# peripherals.net
KiCad netlist of a schematic drawn in Altium Designer
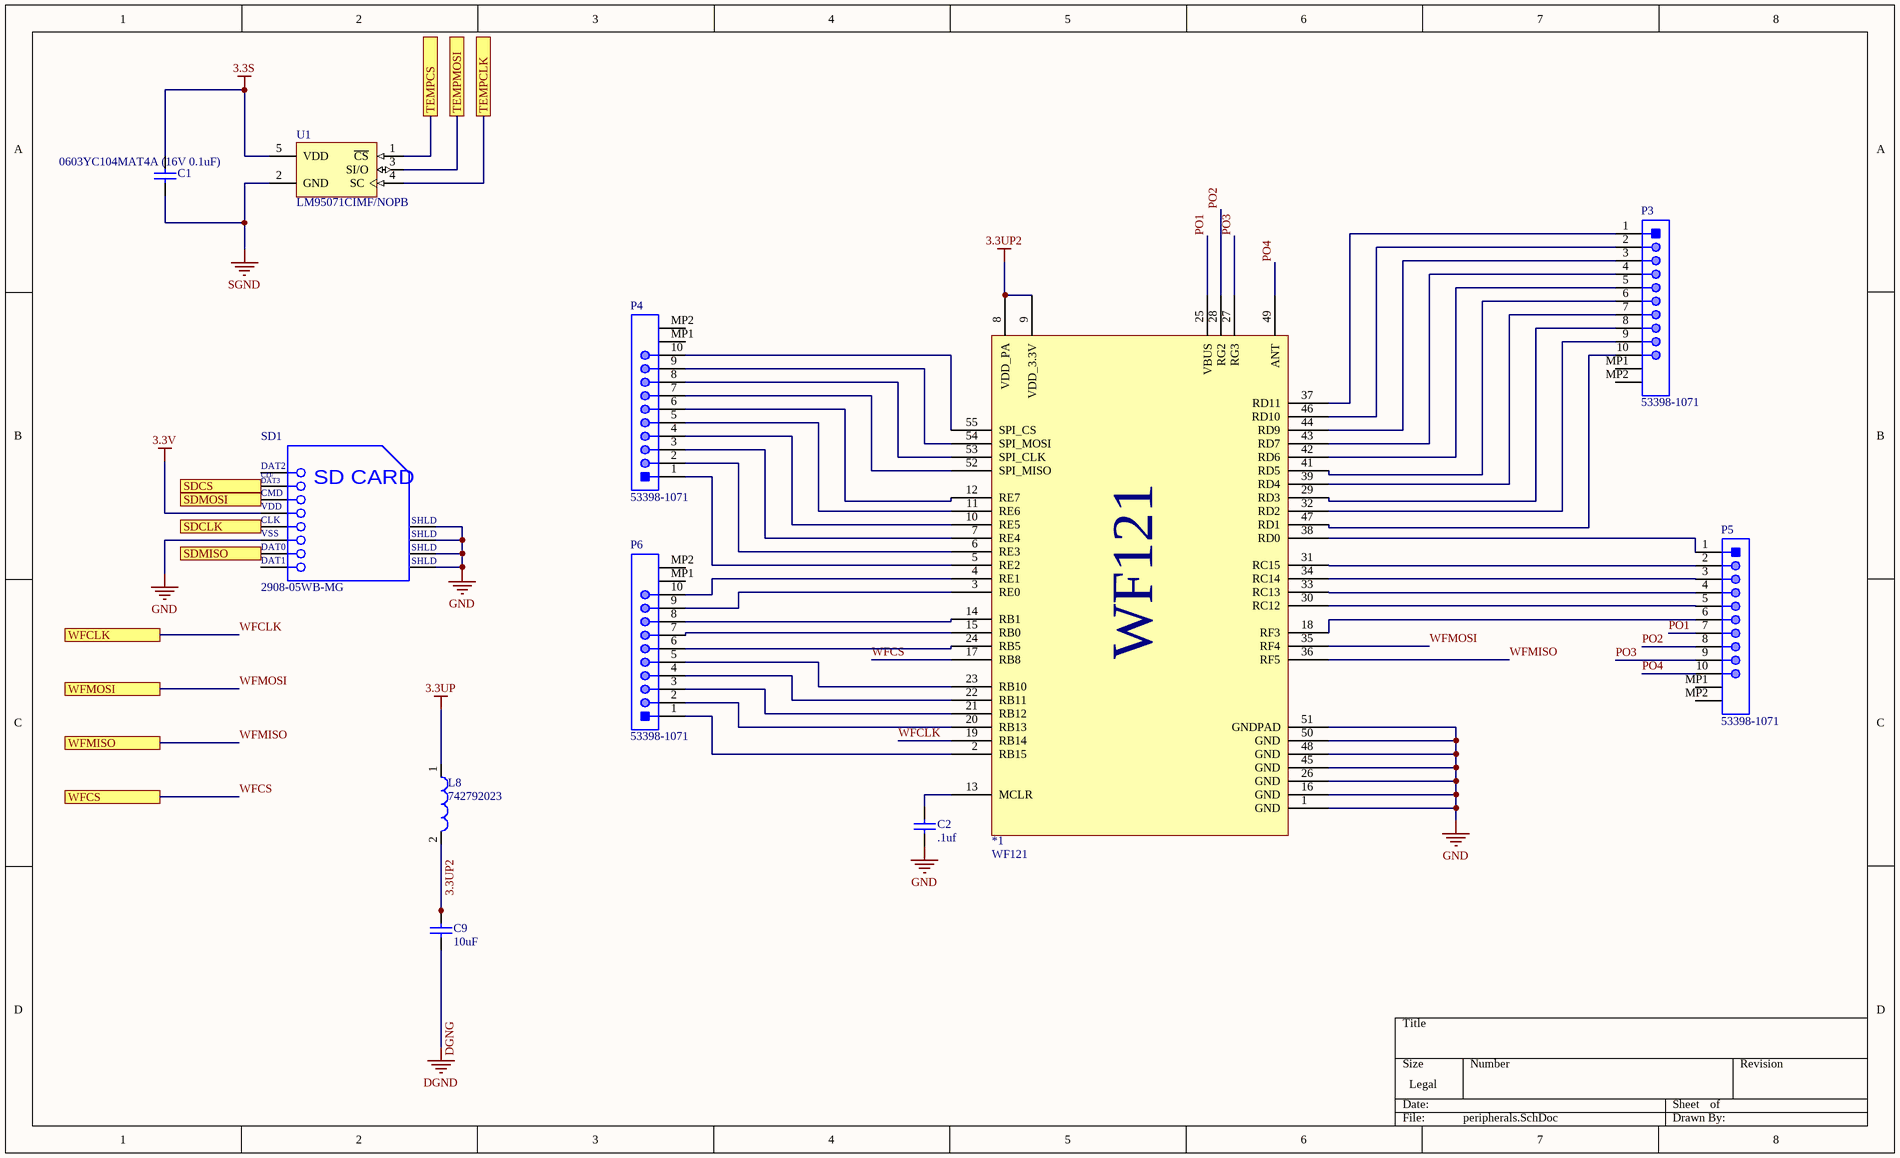
[diagram p0: peripherals.SchDoc]

(export (version "E")
  (design (tool "Eeschema 10.0.6"))
  (components
    (comp (ref "*1")
      (value "WF121")
      (footprint "WF121")
      (description "WF121 WIFI Module.")
      (libsource (lib "WF121") (part "WF121"))
    )
    (comp (ref "C1")
      (value "0603YC104MAT4A (16V 0.1uF)")
      (footprint "CAPC1608X90X35LL15T15")
      (fields
        (field (name "PART NUMBER") "0603YC104MAT4A")
        (field (name "MANUFACTURER") "AVX Interconnect / Elco")
      )
      (libsource (lib "Altium Content Vault") (part "CAP"))
    )
    (comp (ref "C2")
      (value ".1uf")
      (footprint "CAPC2013X94X50NL20T25")
      (fields
        (field (name "PART NUMBER") "0805YC104KAT2A")
        (field (name "MANUFACTURER") "AVX Interconnect / Elco")
      )
      (libsource (lib "Altium Content Vault") (part "CAP"))
    )
    (comp (ref "C9")
      (value "10uF")
      (footprint "CAPC1608X90X35NL10T15")
      (fields (field (name "PART NUMBER") "GRM188R60J106ME47D") (field (name "MANUFACTURER") "Murata"))
      (libsource (lib "Altium Content Vault") (part "CAP"))
    )
    (comp (ref "L8")
      (value "742792023")
      (footprint "SMD-0805")
      (description "SMD EMI Suppression Ferrite Bead WE-CBF, Z = 120 Ohm")
      (libsource (lib "Altium Content Vault") (part "PAS-IND-INDUCTOR-2"))
    )
    (comp (ref "P3")
      (value "53398-1071")
      (footprint "MOLX-53398-1071_V")
      (description "Male Header, Pitch 1.25 mm, 1 x 10 Position, Height 4.7 mm, -40 to 85 degC, RoHS, Tape and Reel")
      (fields (field (name "MANUFACTURER") "Molex"))
      (libsource (lib "") (part "CN-1P-2M-R10_1"))
    )
    (comp (ref "P4")
      (value "53398-1071")
      (footprint "MOLX-53398-1071_V")
      (description "Male Header, Pitch 1.25 mm, 1 x 10 Position, Height 4.7 mm, -40 to 85 degC, RoHS, Tape and Reel")
      (fields (field (name "MANUFACTURER") "Molex"))
      (libsource (lib "Altium Content Vault") (part "CN-1P-2M-R10"))
    )
    (comp (ref "P5")
      (value "53398-1071")
      (footprint "MOLX-53398-1071_V")
      (description "Male Header, Pitch 1.25 mm, 1 x 10 Position, Height 4.7 mm, -40 to 85 degC, RoHS, Tape and Reel")
      (fields (field (name "MANUFACTURER") "Molex"))
      (libsource (lib "") (part "CN-1P-2M-R10_1"))
    )
    (comp (ref "P6")
      (value "53398-1071")
      (footprint "MOLX-53398-1071_V")
      (description "Male Header, Pitch 1.25 mm, 1 x 10 Position, Height 4.7 mm, -40 to 85 degC, RoHS, Tape and Reel")
      (fields (field (name "MANUFACTURER") "Molex"))
      (libsource (lib "Altium Content Vault") (part "CN-1P-2M-R10"))
    )
    (comp (ref "SD1")
      (value "2908-05WB-MG")
      (footprint "3M-2908-05WB-MG_V")
      (description "Card Connector Micro-SD, 500 VAC, 100 mOhm Min, 0.5 A, RoHS, Tape and Reel")
      (fields (field (name "MANUFACTURER") "3M"))
      (libsource (lib "Altium Content Vault") (part "CN-SD-8-4S"))
    )
    (comp (ref "U1")
      (value "LM95071CIMF/NOPB")
      (footprint "DBV0005A_L")
      (description "SPI/MICROWIRE 13-Bit Plus Sign Temperature Sensor, 5-pin SOT-23, Pb-Free")
      (fields (field (name "MANUFACTURER") "Texas Instruments"))
      (libsource (lib "Altium Content Vault") (part "SEN-TEMP-LM95071CIMF-5"))
    )
  )
  (nets
    (net (code "1") (name "/PO1") (class "Default")
      (node (ref "*1") (pin "25") (pinfunction "VBUS_25") (pintype "passive"))
      (node (ref "P5") (pin "7") (pinfunction "7_7") (pintype "passive"))
    )
    (net (code "2") (name "/PO2") (class "Default")
      (node (ref "*1") (pin "28") (pinfunction "RG2_28") (pintype "passive"))
      (node (ref "P5") (pin "8") (pinfunction "8_8") (pintype "passive"))
    )
    (net (code "3") (name "/PO3") (class "Default")
      (node (ref "*1") (pin "27") (pinfunction "RG3_27") (pintype "passive"))
      (node (ref "P5") (pin "9") (pinfunction "9_9") (pintype "passive"))
    )
    (net (code "4") (name "/PO4") (class "Default")
      (node (ref "*1") (pin "49") (pinfunction "ANT_49") (pintype "passive"))
      (node (ref "P5") (pin "10") (pinfunction "10_10") (pintype "passive"))
    )
    (net (code "5") (name "/SDCLK") (class "Default")
      (node (ref "SD1") (pin "5") (pinfunction "CLK_5") (pintype "passive"))
    )
    (net (code "6") (name "/SDCS") (class "Default")
      (node (ref "SD1") (pin "2") (pinfunction "CD/DAT3_2") (pintype "passive"))
    )
    (net (code "7") (name "/SDMISO") (class "Default")
      (node (ref "SD1") (pin "7") (pinfunction "DAT0_7") (pintype "passive"))
    )
    (net (code "8") (name "/SDMOSI") (class "Default")
      (node (ref "SD1") (pin "3") (pinfunction "CMD_3") (pintype "passive"))
    )
    (net (code "9") (name "/TEMPCLK") (class "Default")
      (node (ref "U1") (pin "4") (pinfunction "SC_4") (pintype "input"))
    )
    (net (code "10") (name "/TEMPCS") (class "Default")
      (node (ref "U1") (pin "1") (pinfunction "~{CS}_1") (pintype "input"))
    )
    (net (code "11") (name "/TEMPMOSI") (class "Default")
      (node (ref "U1") (pin "3") (pinfunction "SI/O_3") (pintype "bidirectional"))
    )
    (net (code "12") (name "/WFCLK") (class "Default")
      (node (ref "*1") (pin "19") (pinfunction "RB14_19") (pintype "passive"))
    )
    (net (code "13") (name "/WFCS") (class "Default")
      (node (ref "*1") (pin "17") (pinfunction "RB8_17") (pintype "passive"))
    )
    (net (code "14") (name "/WFMISO") (class "Default")
      (node (ref "*1") (pin "36") (pinfunction "RF5_36") (pintype "passive"))
    )
    (net (code "15") (name "/WFMOSI") (class "Default")
      (node (ref "*1") (pin "35") (pinfunction "RF4_35") (pintype "passive"))
    )
    (net (code "16") (name "3.3S") (class "Default")
      (node (ref "C1") (pin "2") (pinfunction "2_2") (pintype "passive"))
      (node (ref "U1") (pin "5") (pinfunction "VDD_5") (pintype "power_in"))
    )
    (net (code "17") (name "3.3UP") (class "Default")
      (node (ref "L8") (pin "1") (pinfunction "1_1") (pintype "passive"))
    )
    (net (code "18") (name "3.3UP2") (class "Default")
      (node (ref "*1") (pin "8") (pinfunction "VDD_PA_8") (pintype "passive"))
      (node (ref "*1") (pin "9") (pinfunction "VDD_3.3V_9") (pintype "passive"))
      (node (ref "C9") (pin "2") (pinfunction "2_2") (pintype "passive"))
      (node (ref "L8") (pin "2") (pinfunction "2_2") (pintype "passive"))
    )
    (net (code "19") (name "3.3V") (class "Default")
      (node (ref "SD1") (pin "4") (pinfunction "VDD_4") (pintype "passive"))
    )
    (net (code "20") (name "DGND") (class "Default")
      (node (ref "C9") (pin "1") (pinfunction "1_1") (pintype "passive"))
    )
    (net (code "21") (name "GND") (class "Default")
      (node (ref "*1") (pin "1") (pinfunction "GND_1") (pintype "passive"))
      (node (ref "*1") (pin "16") (pinfunction "GND_16") (pintype "passive"))
      (node (ref "*1") (pin "26") (pinfunction "GND_26") (pintype "passive"))
      (node (ref "*1") (pin "45") (pinfunction "GND_45") (pintype "passive"))
      (node (ref "*1") (pin "48") (pinfunction "GND_48") (pintype "passive"))
      (node (ref "*1") (pin "50") (pinfunction "GND_50") (pintype "passive"))
      (node (ref "*1") (pin "51") (pinfunction "GNDPAD_51") (pintype "passive"))
      (node (ref "C2") (pin "1") (pinfunction "1_1") (pintype "passive"))
      (node (ref "SD1") (pin "10") (pinfunction "SHLD_10") (pintype "passive"))
      (node (ref "SD1") (pin "11") (pinfunction "SHLD_11") (pintype "passive"))
      (node (ref "SD1") (pin "12") (pinfunction "SHLD_12") (pintype "passive"))
      (node (ref "SD1") (pin "6") (pinfunction "VSS_6") (pintype "passive"))
      (node (ref "SD1") (pin "9") (pinfunction "SHLD_9") (pintype "passive"))
    )
    (net (code "22") (name "Net-(*1-MCLR)") (class "Default")
      (node (ref "*1") (pin "13") (pinfunction "MCLR_13") (pintype "passive"))
      (node (ref "C2") (pin "2") (pinfunction "2_2") (pintype "passive"))
    )
    (net (code "23") (name "Net-(*1-RB0)") (class "Default")
      (node (ref "*1") (pin "15") (pinfunction "RB0_15") (pintype "passive"))
      (node (ref "P6") (pin "7") (pinfunction "7_7") (pintype "passive"))
    )
    (net (code "24") (name "Net-(*1-RB1)") (class "Default")
      (node (ref "*1") (pin "14") (pinfunction "RB1_14") (pintype "passive"))
      (node (ref "P6") (pin "8") (pinfunction "8_8") (pintype "passive"))
    )
    (net (code "25") (name "Net-(*1-RB5)") (class "Default")
      (node (ref "*1") (pin "24") (pinfunction "RB5_24") (pintype "passive"))
      (node (ref "P6") (pin "6") (pinfunction "6_6") (pintype "passive"))
    )
    (net (code "26") (name "Net-(*1-RB10)") (class "Default")
      (node (ref "*1") (pin "23") (pinfunction "RB10_23") (pintype "passive"))
      (node (ref "P6") (pin "5") (pinfunction "5_5") (pintype "passive"))
    )
    (net (code "27") (name "Net-(*1-RB11)") (class "Default")
      (node (ref "*1") (pin "22") (pinfunction "RB11_22") (pintype "passive"))
      (node (ref "P6") (pin "4") (pinfunction "4_4") (pintype "passive"))
    )
    (net (code "28") (name "Net-(*1-RB12)") (class "Default")
      (node (ref "*1") (pin "21") (pinfunction "RB12_21") (pintype "passive"))
      (node (ref "P6") (pin "3") (pinfunction "3_3") (pintype "passive"))
    )
    (net (code "29") (name "Net-(*1-RB13)") (class "Default")
      (node (ref "*1") (pin "20") (pinfunction "RB13_20") (pintype "passive"))
      (node (ref "P6") (pin "2") (pinfunction "2_2") (pintype "passive"))
    )
    (net (code "30") (name "Net-(*1-RB15)") (class "Default")
      (node (ref "*1") (pin "2") (pinfunction "RB15_2") (pintype "passive"))
      (node (ref "P6") (pin "1") (pinfunction "1_1") (pintype "passive"))
    )
    (net (code "31") (name "Net-(*1-RC12)") (class "Default")
      (node (ref "*1") (pin "30") (pinfunction "RC12_30") (pintype "passive"))
      (node (ref "P5") (pin "5") (pinfunction "5_5") (pintype "passive"))
    )
    (net (code "32") (name "Net-(*1-RC13)") (class "Default")
      (node (ref "*1") (pin "33") (pinfunction "RC13_33") (pintype "passive"))
      (node (ref "P5") (pin "4") (pinfunction "4_4") (pintype "passive"))
    )
    (net (code "33") (name "Net-(*1-RC14)") (class "Default")
      (node (ref "*1") (pin "34") (pinfunction "RC14_34") (pintype "passive"))
      (node (ref "P5") (pin "3") (pinfunction "3_3") (pintype "passive"))
    )
    (net (code "34") (name "Net-(*1-RC15)") (class "Default")
      (node (ref "*1") (pin "31") (pinfunction "RC15_31") (pintype "passive"))
      (node (ref "P5") (pin "2") (pinfunction "2_2") (pintype "passive"))
    )
    (net (code "35") (name "Net-(*1-RD0)") (class "Default")
      (node (ref "*1") (pin "38") (pinfunction "RD0_38") (pintype "passive"))
      (node (ref "P5") (pin "1") (pinfunction "1_1") (pintype "passive"))
    )
    (net (code "36") (name "Net-(*1-RD1)") (class "Default")
      (node (ref "*1") (pin "47") (pinfunction "RD1_47") (pintype "passive"))
      (node (ref "P3") (pin "10") (pinfunction "10_10") (pintype "passive"))
    )
    (net (code "37") (name "Net-(*1-RD2)") (class "Default")
      (node (ref "*1") (pin "32") (pinfunction "RD2_32") (pintype "passive"))
      (node (ref "P3") (pin "9") (pinfunction "9_9") (pintype "passive"))
    )
    (net (code "38") (name "Net-(*1-RD3)") (class "Default")
      (node (ref "*1") (pin "29") (pinfunction "RD3_29") (pintype "passive"))
      (node (ref "P3") (pin "8") (pinfunction "8_8") (pintype "passive"))
    )
    (net (code "39") (name "Net-(*1-RD4)") (class "Default")
      (node (ref "*1") (pin "39") (pinfunction "RD4_39") (pintype "passive"))
      (node (ref "P3") (pin "7") (pinfunction "7_7") (pintype "passive"))
    )
    (net (code "40") (name "Net-(*1-RD5)") (class "Default")
      (node (ref "*1") (pin "41") (pinfunction "RD5_41") (pintype "passive"))
      (node (ref "P3") (pin "6") (pinfunction "6_6") (pintype "passive"))
    )
    (net (code "41") (name "Net-(*1-RD6)") (class "Default")
      (node (ref "*1") (pin "42") (pinfunction "RD6_42") (pintype "passive"))
      (node (ref "P3") (pin "5") (pinfunction "5_5") (pintype "passive"))
    )
    (net (code "42") (name "Net-(*1-RD7)") (class "Default")
      (node (ref "*1") (pin "43") (pinfunction "RD7_43") (pintype "passive"))
      (node (ref "P3") (pin "4") (pinfunction "4_4") (pintype "passive"))
    )
    (net (code "43") (name "Net-(*1-RD9)") (class "Default")
      (node (ref "*1") (pin "44") (pinfunction "RD9_44") (pintype "passive"))
      (node (ref "P3") (pin "3") (pinfunction "3_3") (pintype "passive"))
    )
    (net (code "44") (name "Net-(*1-RD10)") (class "Default")
      (node (ref "*1") (pin "46") (pinfunction "RD10_46") (pintype "passive"))
      (node (ref "P3") (pin "2") (pinfunction "2_2") (pintype "passive"))
    )
    (net (code "45") (name "Net-(*1-RD11)") (class "Default")
      (node (ref "*1") (pin "37") (pinfunction "RD11_37") (pintype "passive"))
      (node (ref "P3") (pin "1") (pinfunction "1_1") (pintype "passive"))
    )
    (net (code "46") (name "Net-(*1-RE0)") (class "Default")
      (node (ref "*1") (pin "3") (pinfunction "RE0_3") (pintype "passive"))
      (node (ref "P6") (pin "9") (pinfunction "9_9") (pintype "passive"))
    )
    (net (code "47") (name "Net-(*1-RE1)") (class "Default")
      (node (ref "*1") (pin "4") (pinfunction "RE1_4") (pintype "passive"))
      (node (ref "P6") (pin "10") (pinfunction "10_10") (pintype "passive"))
    )
    (net (code "48") (name "Net-(*1-RE2)") (class "Default")
      (node (ref "*1") (pin "5") (pinfunction "RE2_5") (pintype "passive"))
      (node (ref "P4") (pin "1") (pinfunction "1_1") (pintype "passive"))
    )
    (net (code "49") (name "Net-(*1-RE3)") (class "Default")
      (node (ref "*1") (pin "6") (pinfunction "RE3_6") (pintype "passive"))
      (node (ref "P4") (pin "2") (pinfunction "2_2") (pintype "passive"))
    )
    (net (code "50") (name "Net-(*1-RE4)") (class "Default")
      (node (ref "*1") (pin "7") (pinfunction "RE4_7") (pintype "passive"))
      (node (ref "P4") (pin "3") (pinfunction "3_3") (pintype "passive"))
    )
    (net (code "51") (name "Net-(*1-RE5)") (class "Default")
      (node (ref "*1") (pin "10") (pinfunction "RE5_10") (pintype "passive"))
      (node (ref "P4") (pin "4") (pinfunction "4_4") (pintype "passive"))
    )
    (net (code "52") (name "Net-(*1-RE6)") (class "Default")
      (node (ref "*1") (pin "11") (pinfunction "RE6_11") (pintype "passive"))
      (node (ref "P4") (pin "5") (pinfunction "5_5") (pintype "passive"))
    )
    (net (code "53") (name "Net-(*1-RE7)") (class "Default")
      (node (ref "*1") (pin "12") (pinfunction "RE7_12") (pintype "passive"))
      (node (ref "P4") (pin "6") (pinfunction "6_6") (pintype "passive"))
    )
    (net (code "54") (name "Net-(*1-RF3)") (class "Default")
      (node (ref "*1") (pin "18") (pinfunction "RF3_18") (pintype "passive"))
      (node (ref "P5") (pin "6") (pinfunction "6_6") (pintype "passive"))
    )
    (net (code "55") (name "Net-(*1-SPI_CLK)") (class "Default")
      (node (ref "*1") (pin "53") (pinfunction "SPI_CLK_53") (pintype "passive"))
      (node (ref "P4") (pin "8") (pinfunction "8_8") (pintype "passive"))
    )
    (net (code "56") (name "Net-(*1-SPI_CS)") (class "Default")
      (node (ref "*1") (pin "55") (pinfunction "SPI_CS_55") (pintype "passive"))
      (node (ref "P4") (pin "10") (pinfunction "10_10") (pintype "passive"))
    )
    (net (code "57") (name "Net-(*1-SPI_MISO)") (class "Default")
      (node (ref "*1") (pin "52") (pinfunction "SPI_MISO_52") (pintype "passive"))
      (node (ref "P4") (pin "7") (pinfunction "7_7") (pintype "passive"))
    )
    (net (code "58") (name "Net-(*1-SPI_MOSI)") (class "Default")
      (node (ref "*1") (pin "54") (pinfunction "SPI_MOSI_54") (pintype "passive"))
      (node (ref "P4") (pin "9") (pinfunction "9_9") (pintype "passive"))
    )
    (net (code "59") (name "SGND") (class "Default")
      (node (ref "C1") (pin "1") (pinfunction "1_1") (pintype "passive"))
      (node (ref "U1") (pin "2") (pinfunction "GND_2") (pintype "power_in"))
    )
    (net (code "60") (name "unconnected-(P3-PadMP1)") (class "Default")
      (node (ref "P3") (pin "MP1") (pinfunction "MP1_MP1") (pintype "passive"))
    )
    (net (code "61") (name "unconnected-(P3-PadMP2)") (class "Default")
      (node (ref "P3") (pin "MP2") (pinfunction "MP2_MP2") (pintype "passive"))
    )
    (net (code "62") (name "unconnected-(P4-PadMP1)") (class "Default")
      (node (ref "P4") (pin "MP1") (pinfunction "MP1_MP1") (pintype "passive"))
    )
    (net (code "63") (name "unconnected-(P4-PadMP2)") (class "Default")
      (node (ref "P4") (pin "MP2") (pinfunction "MP2_MP2") (pintype "passive"))
    )
    (net (code "64") (name "unconnected-(P5-PadMP1)") (class "Default")
      (node (ref "P5") (pin "MP1") (pinfunction "MP1_MP1") (pintype "passive"))
    )
    (net (code "65") (name "unconnected-(P5-PadMP2)") (class "Default")
      (node (ref "P5") (pin "MP2") (pinfunction "MP2_MP2") (pintype "passive"))
    )
    (net (code "66") (name "unconnected-(P6-PadMP1)") (class "Default")
      (node (ref "P6") (pin "MP1") (pinfunction "MP1_MP1") (pintype "passive"))
    )
    (net (code "67") (name "unconnected-(P6-PadMP2)") (class "Default")
      (node (ref "P6") (pin "MP2") (pinfunction "MP2_MP2") (pintype "passive"))
    )
    (net (code "68") (name "unconnected-(SD1-DAT1-Pad8)") (class "Default")
      (node (ref "SD1") (pin "8") (pinfunction "DAT1_8") (pintype "passive"))
    )
    (net (code "69") (name "unconnected-(SD1-DAT2-Pad1)") (class "Default")
      (node (ref "SD1") (pin "1") (pinfunction "DAT2_1") (pintype "passive"))
    )
  )
)
